# AutoLevel_Module_V2.net
KiCad netlist of a schematic drawn in EAGLE
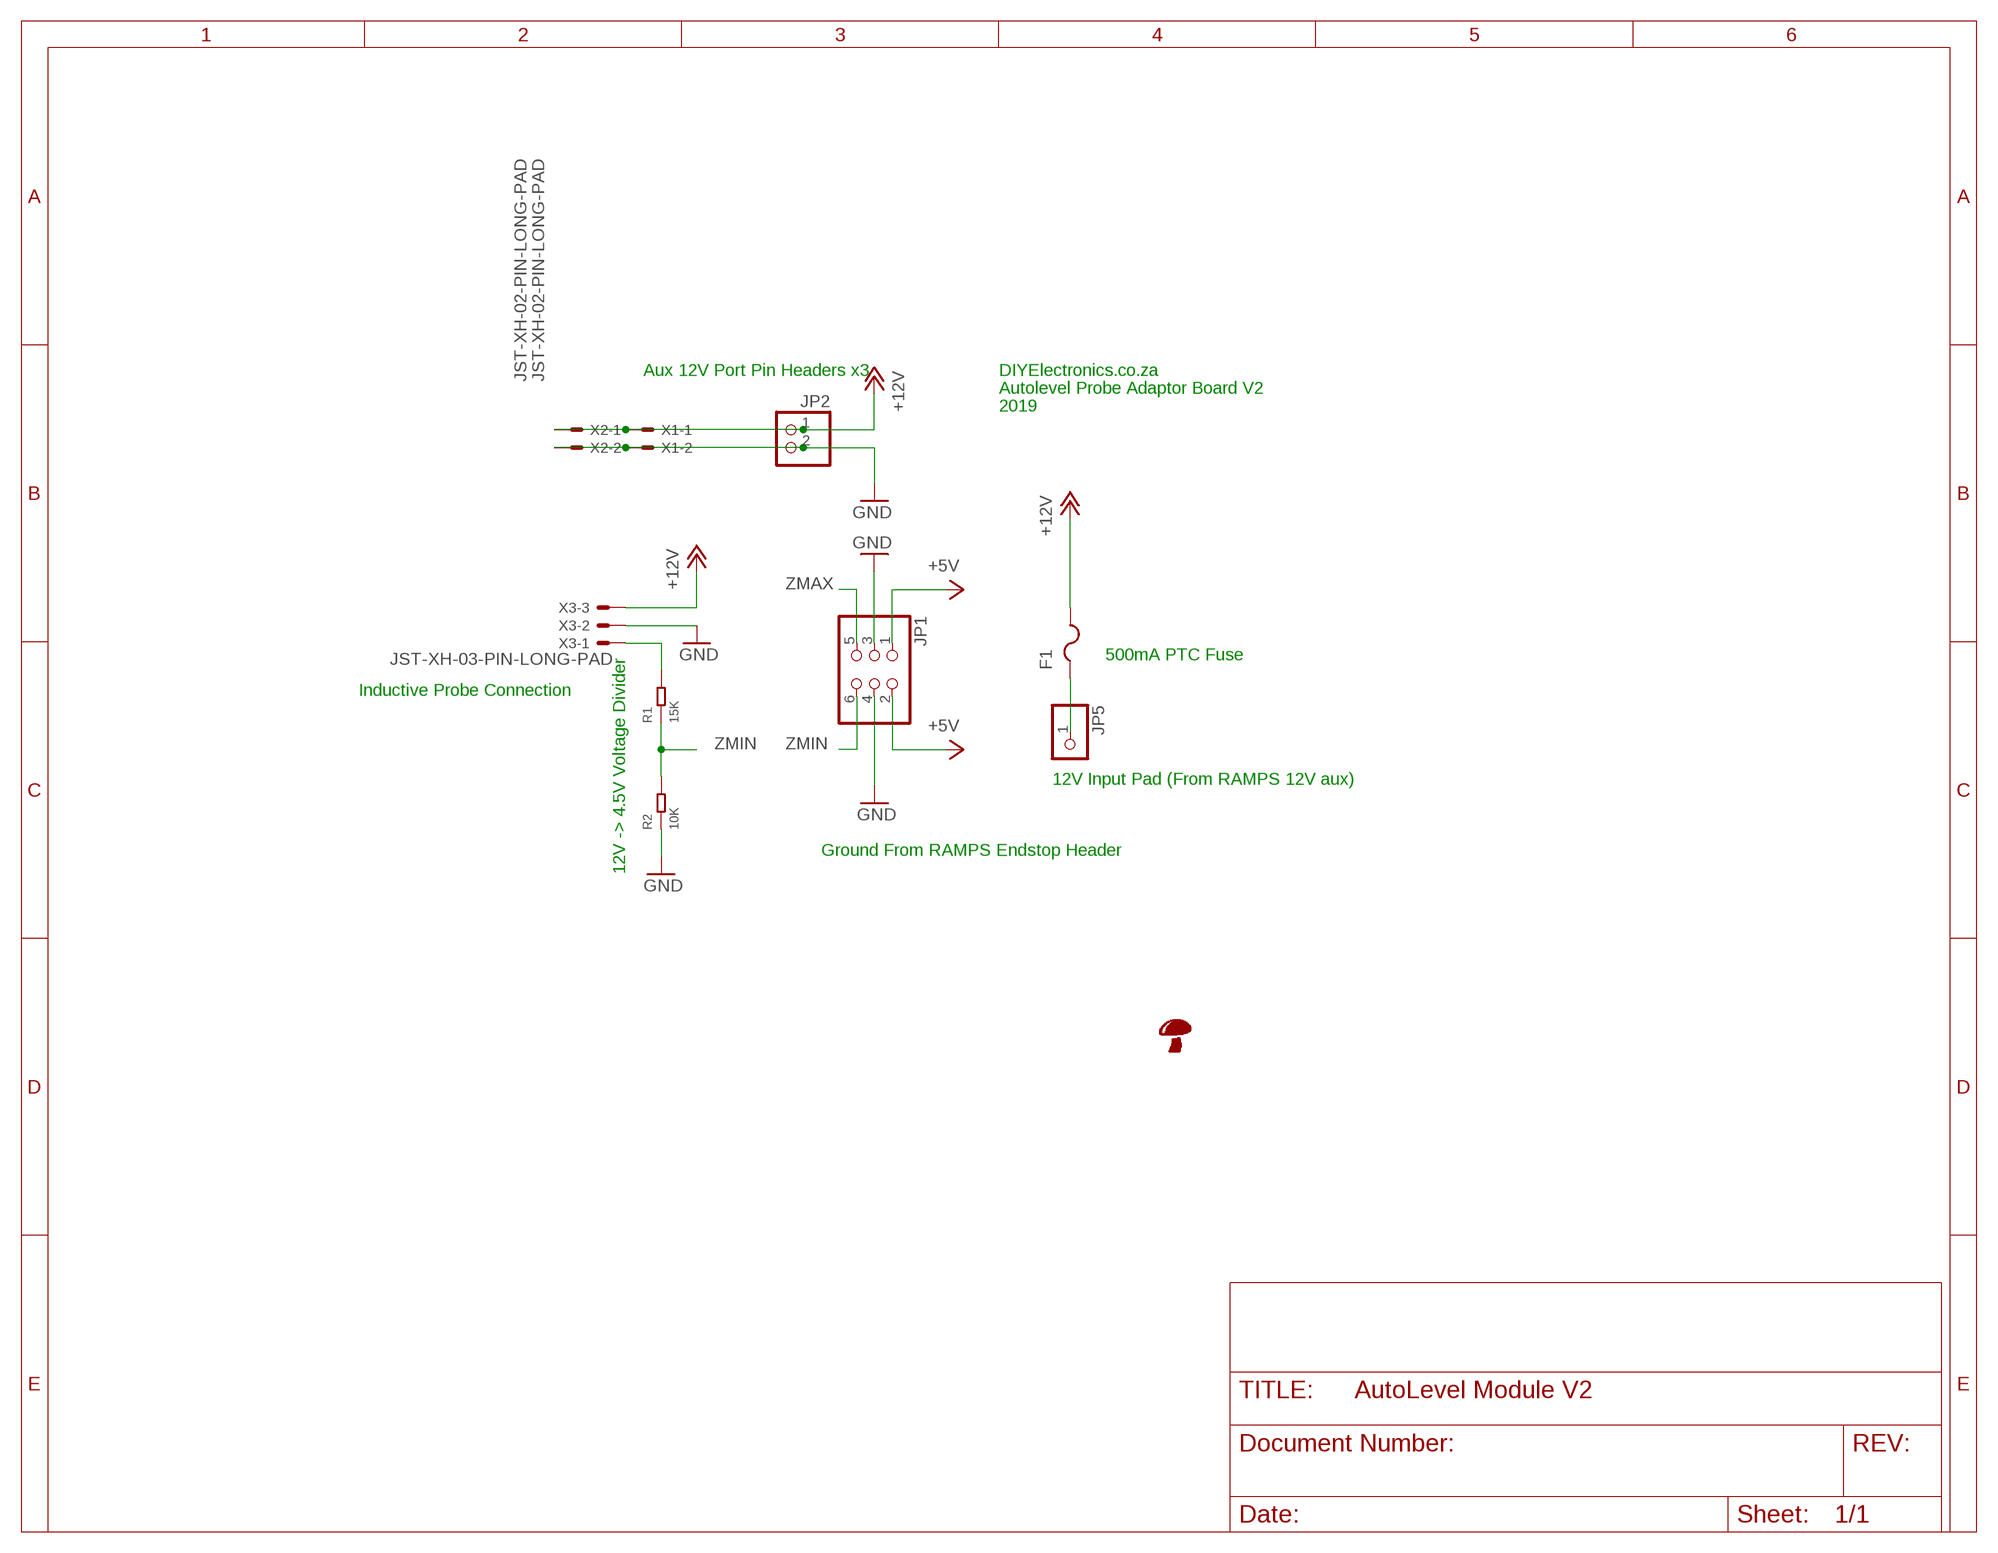
[diagram p0: schematic, sheet 1]

(export (version "E")
  (design (tool "Eeschema 10.0.6"))
  (components
    (comp (ref "F1")
      (value "PTCFUSE-1812")
      (footprint "eagle-import:1812")
      (libsource (lib "eagle-import") (part "PTCFUSE-1812"))
    )
    (comp (ref "JP1")
      (value "PINHD-2X3")
      (footprint "eagle-import:2X03")
      (libsource (lib "eagle-import") (part "PINHD-2X3"))
    )
    (comp (ref "JP2")
      (value "PINHD-1X2")
      (footprint "eagle-import:1X02")
      (libsource (lib "eagle-import") (part "PINHD-1X2"))
    )
    (comp (ref "JP5")
      (value "PINHD-1X1")
      (footprint "eagle-import:1X01")
      (libsource (lib "eagle-import") (part "PINHD-1X1"))
    )
    (comp (ref "R1")
      (value "15K")
      (footprint "eagle-import:R0805")
      (fields (field (name "MPN") "RC0805JR-071KL"))
      (libsource (lib "eagle-import") (part "SMD-RES-15K-5%-1/8W(0805)"))
    )
    (comp (ref "R2")
      (value "10K")
      (footprint "eagle-import:R0805")
      (fields (field (name "MPN") "RC0805FR-0710KL"))
      (libsource (lib "eagle-import") (part "SMD-RES-10K-1%-1/8W(0805)"))
    )
    (comp (ref "U$2")
      (value "SHROOMBOTTOMSILK")
      (footprint "eagle-import:SHROOM_BS")
      (libsource (lib "eagle-import") (part "SHROOMBOTTOMSILK"))
    )
    (comp (ref "X1")
      (value "JST-XH-02-PIN-LONG-PAD")
      (footprint "eagle-import:JST-XH-02-PACKAGE-LONG-PAD")
      (libsource (lib "eagle-import") (part "JST-XH-02-PIN-LONG-PAD"))
    )
    (comp (ref "X2")
      (value "JST-XH-02-PIN-LONG-PAD")
      (footprint "eagle-import:JST-XH-02-PACKAGE-LONG-PAD")
      (libsource (lib "eagle-import") (part "JST-XH-02-PIN-LONG-PAD"))
    )
    (comp (ref "X3")
      (value "JST-XH-03-PIN-LONG-PAD")
      (footprint "eagle-import:JST-XH-03-PACKAGE-LONG-PAD")
      (libsource (lib "eagle-import") (part "JST-XH-03-PIN-LONG-PAD"))
    )
  )
  (nets
    (net (code "1") (name "+5V") (class "Default")
      (node (ref "JP1") (pin "1") (pinfunction "1_1") (pintype "passive"))
      (node (ref "JP1") (pin "2") (pinfunction "2_2") (pintype "passive"))
    )
    (net (code "2") (name "+12V") (class "Default")
      (node (ref "F1") (pin "2") (pinfunction "2_2") (pintype "passive"))
      (node (ref "JP2") (pin "1") (pinfunction "1_1") (pintype "passive"))
      (node (ref "X1") (pin "1") (pinfunction "S_1") (pintype "passive"))
      (node (ref "X2") (pin "1") (pinfunction "S_1") (pintype "passive"))
      (node (ref "X3") (pin "3") (pinfunction "S_3") (pintype "passive"))
    )
    (net (code "3") (name "/ZMAX") (class "Default")
      (node (ref "JP1") (pin "5") (pinfunction "5_5") (pintype "passive"))
    )
    (net (code "4") (name "/ZMIN") (class "Default")
      (node (ref "JP1") (pin "6") (pinfunction "6_6") (pintype "passive"))
      (node (ref "R1") (pin "1") (pinfunction "1_1") (pintype "passive"))
      (node (ref "R2") (pin "2") (pinfunction "2_2") (pintype "passive"))
    )
    (net (code "5") (name "GND") (class "Default")
      (node (ref "JP1") (pin "3") (pinfunction "3_3") (pintype "passive"))
      (node (ref "JP1") (pin "4") (pinfunction "4_4") (pintype "passive"))
      (node (ref "JP2") (pin "2") (pinfunction "2_2") (pintype "passive"))
      (node (ref "R2") (pin "1") (pinfunction "1_1") (pintype "passive"))
      (node (ref "X1") (pin "2") (pinfunction "S_2") (pintype "passive"))
      (node (ref "X2") (pin "2") (pinfunction "S_2") (pintype "passive"))
      (node (ref "X3") (pin "2") (pinfunction "S_2") (pintype "passive"))
    )
    (net (code "6") (name "Net-(F1-Pad1)") (class "Default")
      (node (ref "F1") (pin "1") (pinfunction "1_1") (pintype "passive"))
      (node (ref "JP5") (pin "1") (pinfunction "1_1") (pintype "passive"))
    )
    (net (code "7") (name "Net-(X3A-S)") (class "Default")
      (node (ref "R1") (pin "2") (pinfunction "2_2") (pintype "passive"))
      (node (ref "X3") (pin "1") (pinfunction "S_1") (pintype "passive"))
    )
  )
)
